# esp_dht.net
KiCad netlist of a schematic drawn in EAGLE
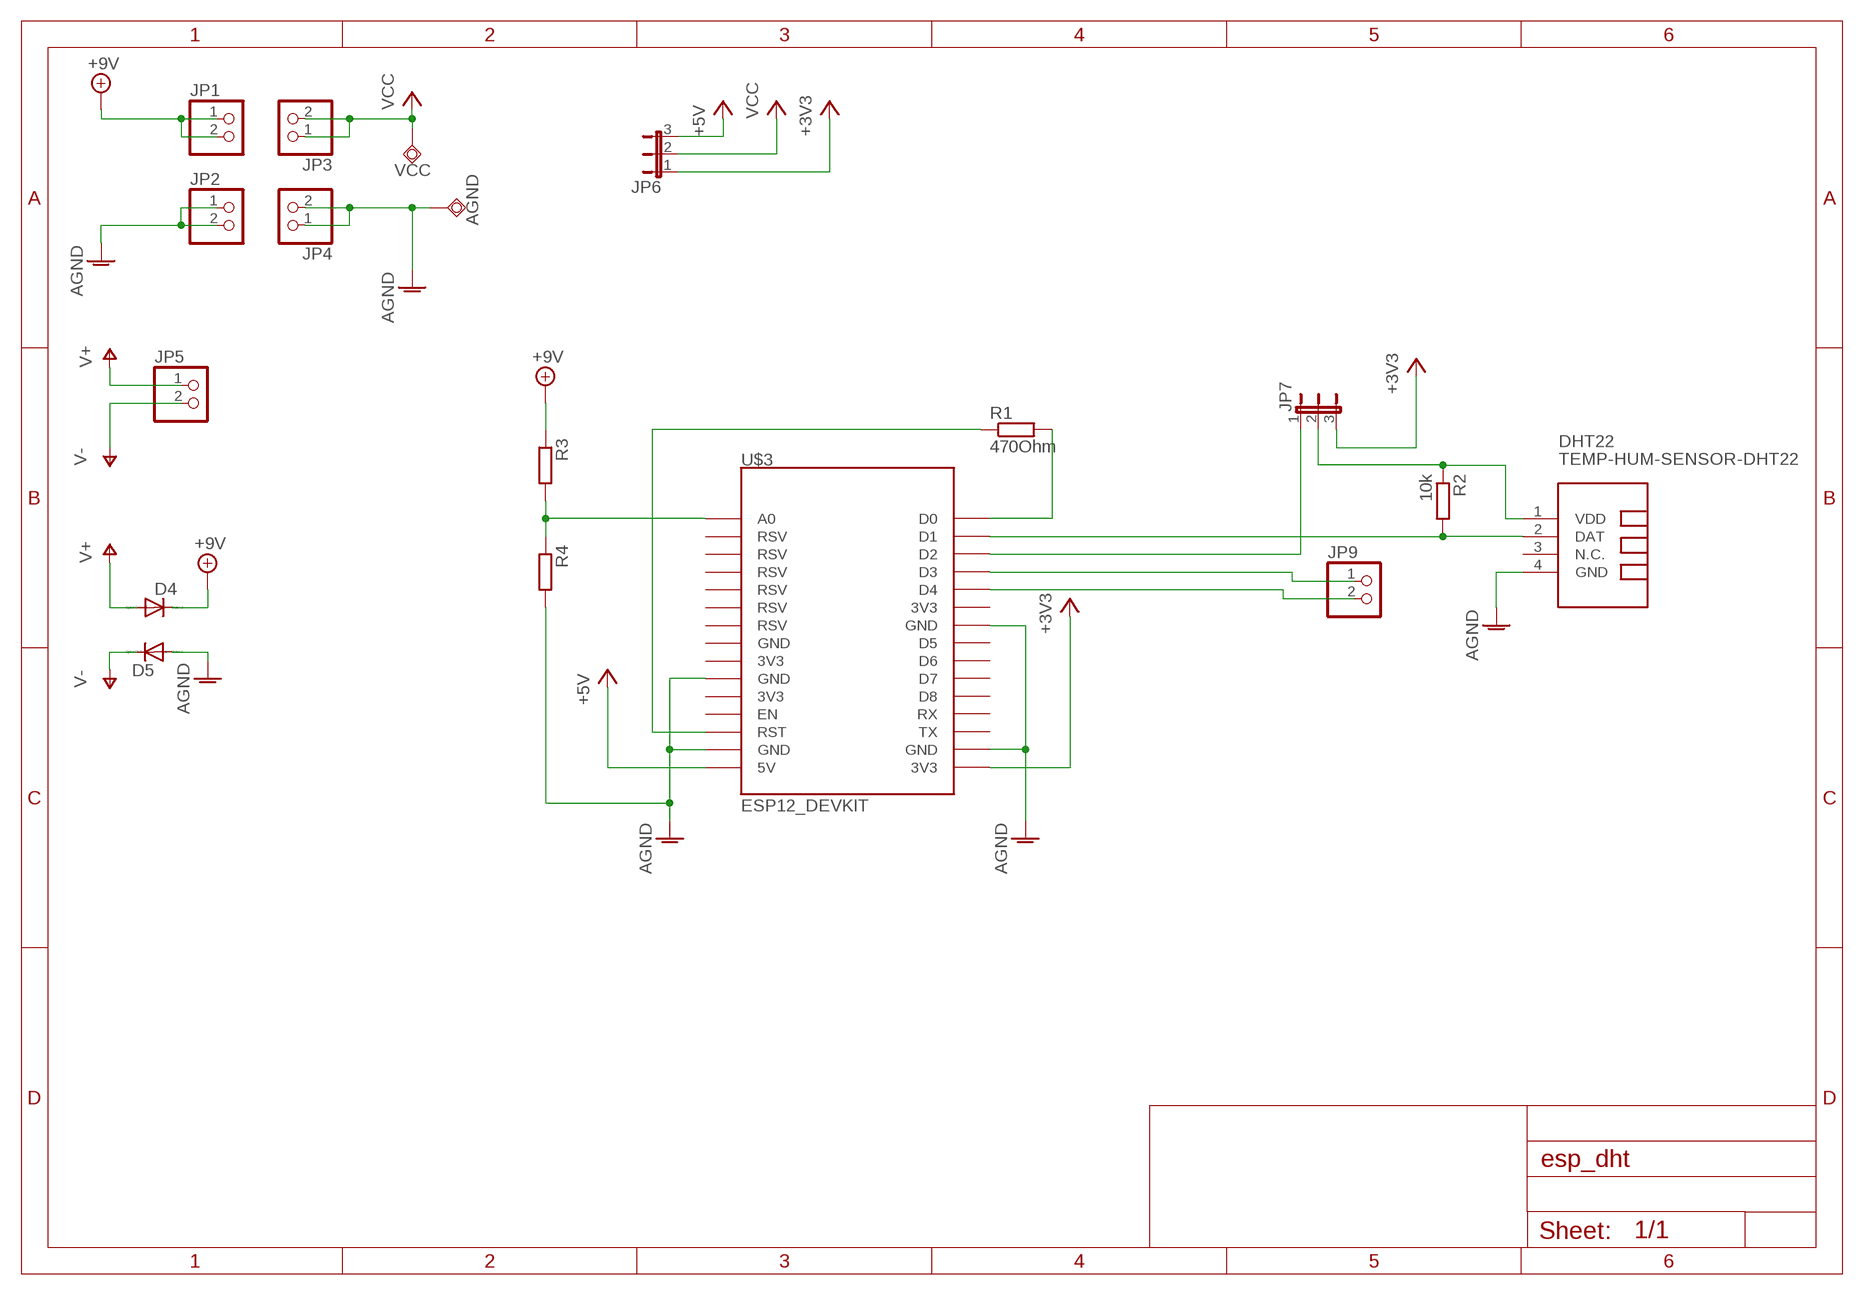
[diagram p0: schematic, sheet 1]

(export (version "E")
  (design (tool "Eeschema 10.0.6"))
  (components
    (comp (ref "AGND")
      (value "TPSQTP20SQ")
      (footprint "eagle-import:TP20SQ")
      (libsource (lib "eagle-import") (part "TPSQTP20SQ"))
    )
    (comp (ref "D4")
      (value "1N4148DO35-7")
      (footprint "eagle-import:DO35-7")
      (libsource (lib "eagle-import") (part "1N4148DO35-7"))
    )
    (comp (ref "D5")
      (value "1N4148DO35-7")
      (footprint "eagle-import:DO35-7")
      (libsource (lib "eagle-import") (part "1N4148DO35-7"))
    )
    (comp (ref "DHT22")
      (value "TEMP-HUM-SENSOR-DHT22")
      (footprint "eagle-import:TEMP-HUM-SENSOR-DHT22")
      (libsource (lib "eagle-import") (part "TEMP-HUM-SENSOR-DHT22"))
    )
    (comp (ref "JP1")
      (value "PINHD-1X2")
      (footprint "eagle-import:1X02")
      (libsource (lib "eagle-import") (part "PINHD-1X2"))
    )
    (comp (ref "JP2")
      (value "PINHD-1X2")
      (footprint "eagle-import:1X02")
      (libsource (lib "eagle-import") (part "PINHD-1X2"))
    )
    (comp (ref "JP3")
      (value "PINHD-1X2")
      (footprint "eagle-import:1X02")
      (libsource (lib "eagle-import") (part "PINHD-1X2"))
    )
    (comp (ref "JP4")
      (value "PINHD-1X2")
      (footprint "eagle-import:1X02")
      (libsource (lib "eagle-import") (part "PINHD-1X2"))
    )
    (comp (ref "JP5")
      (value "PINHD-1X2")
      (footprint "eagle-import:1X02")
      (libsource (lib "eagle-import") (part "PINHD-1X2"))
    )
    (comp (ref "JP6")
      (value "JP2E")
      (footprint "eagle-import:JP2")
      (libsource (lib "eagle-import") (part "JP2E"))
    )
    (comp (ref "JP7")
      (value "JP2E")
      (footprint "eagle-import:JP2")
      (libsource (lib "eagle-import") (part "JP2E"))
    )
    (comp (ref "JP9")
      (value "PINHD-1X2")
      (footprint "eagle-import:1X02")
      (libsource (lib "eagle-import") (part "PINHD-1X2"))
    )
    (comp (ref "R1")
      (value "470Ohm")
      (footprint "eagle-import:R0805")
      (libsource (lib "eagle-import") (part "R-EU_R0805"))
    )
    (comp (ref "R2")
      (value "10k")
      (footprint "eagle-import:R0805")
      (libsource (lib "eagle-import") (part "R-EU_R0805"))
    )
    (comp (ref "R3")
      (value "R-EU_R0805")
      (footprint "eagle-import:R0805")
      (libsource (lib "eagle-import") (part "R-EU_R0805"))
    )
    (comp (ref "R4")
      (value "R-EU_R0805")
      (footprint "eagle-import:R0805")
      (libsource (lib "eagle-import") (part "R-EU_R0805"))
    )
    (comp (ref "U$3")
      (value "ESP12_DEVKIT")
      (footprint "eagle-import:ESP12_DEVKIT")
      (libsource (lib "eagle-import") (part "ESP12_DEVKIT"))
    )
    (comp (ref "VCC")
      (value "TPSQTP20SQ")
      (footprint "eagle-import:TP20SQ")
      (libsource (lib "eagle-import") (part "TPSQTP20SQ"))
    )
  )
  (nets
    (net (code "1") (name "+3V3") (class "Default")
      (node (ref "JP6") (pin "1") (pinfunction "1_1") (pintype "passive"))
      (node (ref "JP7") (pin "3") (pinfunction "3_3") (pintype "passive"))
      (node (ref "U$3") (pin "3V3@2") (pinfunction "3V3_3V3@2") (pintype "bidirectional"))
    )
    (net (code "2") (name "+5V") (class "Default")
      (node (ref "JP6") (pin "3") (pinfunction "3_3") (pintype "passive"))
      (node (ref "U$3") (pin "5V") (pinfunction "5V_5V") (pintype "bidirectional"))
    )
    (net (code "3") (name "+9V") (class "Default")
      (node (ref "D4") (pin "C") (pinfunction "C_C") (pintype "passive"))
      (node (ref "JP1") (pin "1") (pinfunction "1_1") (pintype "passive"))
      (node (ref "JP1") (pin "2") (pinfunction "2_2") (pintype "passive"))
      (node (ref "R3") (pin "1") (pinfunction "1_1") (pintype "passive"))
    )
    (net (code "4") (name "AGND") (class "Default")
      (node (ref "AGND") (pin "TP") (pinfunction "TP_TP") (pintype "input"))
      (node (ref "D5") (pin "A") (pinfunction "A_A") (pintype "passive"))
      (node (ref "DHT22") (pin "4") (pinfunction "GND_4") (pintype "power_in"))
      (node (ref "JP2") (pin "1") (pinfunction "1_1") (pintype "passive"))
      (node (ref "JP2") (pin "2") (pinfunction "2_2") (pintype "passive"))
      (node (ref "JP4") (pin "1") (pinfunction "1_1") (pintype "passive"))
      (node (ref "JP4") (pin "2") (pinfunction "2_2") (pintype "passive"))
      (node (ref "R4") (pin "2") (pinfunction "2_2") (pintype "passive"))
      (node (ref "U$3") (pin "GND@0") (pinfunction "GND_GND@0") (pintype "bidirectional"))
      (node (ref "U$3") (pin "GND@1") (pinfunction "GND_GND@1") (pintype "bidirectional"))
      (node (ref "U$3") (pin "GND@2") (pinfunction "GND_GND@2") (pintype "bidirectional"))
      (node (ref "U$3") (pin "GND@3") (pinfunction "GND_GND@3") (pintype "bidirectional"))
    )
    (net (code "5") (name "Net-(DHT22-DAT)") (class "Default")
      (node (ref "DHT22") (pin "2") (pinfunction "DAT_2") (pintype "bidirectional"))
      (node (ref "R2") (pin "2") (pinfunction "2_2") (pintype "passive"))
      (node (ref "U$3") (pin "D1") (pinfunction "D1_D1") (pintype "bidirectional"))
    )
    (net (code "6") (name "Net-(DHT22-VDD)") (class "Default")
      (node (ref "DHT22") (pin "1") (pinfunction "VDD_1") (pintype "power_in"))
      (node (ref "JP7") (pin "2") (pinfunction "2_2") (pintype "passive"))
      (node (ref "R2") (pin "1") (pinfunction "1_1") (pintype "passive"))
    )
    (net (code "7") (name "Net-(JP7-Pad1)") (class "Default")
      (node (ref "JP7") (pin "1") (pinfunction "1_1") (pintype "passive"))
      (node (ref "U$3") (pin "D2") (pinfunction "D2_D2") (pintype "bidirectional"))
    )
    (net (code "8") (name "Net-(JP9-Pad1)") (class "Default")
      (node (ref "JP9") (pin "1") (pinfunction "1_1") (pintype "passive"))
      (node (ref "U$3") (pin "D3") (pinfunction "D3_D3") (pintype "bidirectional"))
    )
    (net (code "9") (name "Net-(JP9-Pad2)") (class "Default")
      (node (ref "JP9") (pin "2") (pinfunction "2_2") (pintype "passive"))
      (node (ref "U$3") (pin "D4") (pinfunction "D4_D4") (pintype "bidirectional"))
    )
    (net (code "10") (name "Net-(R1-Pad1)") (class "Default")
      (node (ref "R1") (pin "1") (pinfunction "1_1") (pintype "passive"))
      (node (ref "U$3") (pin "RST") (pinfunction "RST_RST") (pintype "bidirectional"))
    )
    (net (code "11") (name "Net-(R1-Pad2)") (class "Default")
      (node (ref "R1") (pin "2") (pinfunction "2_2") (pintype "passive"))
      (node (ref "U$3") (pin "D0") (pinfunction "D0_D0") (pintype "bidirectional"))
    )
    (net (code "12") (name "Net-(R3-Pad2)") (class "Default")
      (node (ref "R3") (pin "2") (pinfunction "2_2") (pintype "passive"))
      (node (ref "R4") (pin "1") (pinfunction "1_1") (pintype "passive"))
      (node (ref "U$3") (pin "A0") (pinfunction "A0_A0") (pintype "bidirectional"))
    )
    (net (code "13") (name "V+") (class "Default")
      (node (ref "D4") (pin "A") (pinfunction "A_A") (pintype "passive"))
      (node (ref "JP5") (pin "1") (pinfunction "1_1") (pintype "passive"))
    )
    (net (code "14") (name "V-") (class "Default")
      (node (ref "D5") (pin "C") (pinfunction "C_C") (pintype "passive"))
      (node (ref "JP5") (pin "2") (pinfunction "2_2") (pintype "passive"))
    )
    (net (code "15") (name "VCC") (class "Default")
      (node (ref "JP3") (pin "1") (pinfunction "1_1") (pintype "passive"))
      (node (ref "JP3") (pin "2") (pinfunction "2_2") (pintype "passive"))
      (node (ref "JP6") (pin "2") (pinfunction "2_2") (pintype "passive"))
      (node (ref "VCC") (pin "TP") (pinfunction "TP_TP") (pintype "input"))
    )
    (net (code "16") (name "unconnected-(DHT22-N.C.-Pad3)") (class "Default")
      (node (ref "DHT22") (pin "3") (pinfunction "N.C._3") (pintype "passive"))
    )
    (net (code "17") (name "unconnected-(U$3-3V3-Pad3V3@0)") (class "Default")
      (node (ref "U$3") (pin "3V3@0") (pinfunction "3V3_3V3@0") (pintype "bidirectional"))
    )
    (net (code "18") (name "unconnected-(U$3-3V3-Pad3V3@1)") (class "Default")
      (node (ref "U$3") (pin "3V3@1") (pinfunction "3V3_3V3@1") (pintype "bidirectional"))
    )
    (net (code "19") (name "unconnected-(U$3-3V3-Pad3V3@3)") (class "Default")
      (node (ref "U$3") (pin "3V3@3") (pinfunction "3V3_3V3@3") (pintype "bidirectional"))
    )
    (net (code "20") (name "unconnected-(U$3-GND-PadGND@4)") (class "Default")
      (node (ref "U$3") (pin "GND@4") (pinfunction "GND_GND@4") (pintype "bidirectional"))
    )
    (net (code "21") (name "unconnected-(U$3-PadD5)") (class "Default")
      (node (ref "U$3") (pin "D5") (pinfunction "D5_D5") (pintype "bidirectional"))
    )
    (net (code "22") (name "unconnected-(U$3-PadD6)") (class "Default")
      (node (ref "U$3") (pin "D6") (pinfunction "D6_D6") (pintype "bidirectional"))
    )
    (net (code "23") (name "unconnected-(U$3-PadD7)") (class "Default")
      (node (ref "U$3") (pin "D7") (pinfunction "D7_D7") (pintype "bidirectional"))
    )
    (net (code "24") (name "unconnected-(U$3-PadD8)") (class "Default")
      (node (ref "U$3") (pin "D8") (pinfunction "D8_D8") (pintype "bidirectional"))
    )
    (net (code "25") (name "unconnected-(U$3-PadEN)") (class "Default")
      (node (ref "U$3") (pin "EN") (pinfunction "EN_EN") (pintype "bidirectional"))
    )
    (net (code "26") (name "unconnected-(U$3-PadRX)") (class "Default")
      (node (ref "U$3") (pin "RX") (pinfunction "RX_RX") (pintype "bidirectional"))
    )
    (net (code "27") (name "unconnected-(U$3-PadTX)") (class "Default")
      (node (ref "U$3") (pin "TX") (pinfunction "TX_TX") (pintype "bidirectional"))
    )
    (net (code "28") (name "unconnected-(U$3-RSV-PadRSV@0)") (class "Default")
      (node (ref "U$3") (pin "RSV@0") (pinfunction "RSV_RSV@0") (pintype "bidirectional"))
    )
    (net (code "29") (name "unconnected-(U$3-RSV-PadRSV@1)") (class "Default")
      (node (ref "U$3") (pin "RSV@1") (pinfunction "RSV_RSV@1") (pintype "bidirectional"))
    )
    (net (code "30") (name "unconnected-(U$3-RSV-PadRSV@2)") (class "Default")
      (node (ref "U$3") (pin "RSV@2") (pinfunction "RSV_RSV@2") (pintype "bidirectional"))
    )
    (net (code "31") (name "unconnected-(U$3-RSV-PadRSV@3)") (class "Default")
      (node (ref "U$3") (pin "RSV@3") (pinfunction "RSV_RSV@3") (pintype "bidirectional"))
    )
    (net (code "32") (name "unconnected-(U$3-RSV-PadRSV@4)") (class "Default")
      (node (ref "U$3") (pin "RSV@4") (pinfunction "RSV_RSV@4") (pintype "bidirectional"))
    )
    (net (code "33") (name "unconnected-(U$3-RSV-PadRSV@5)") (class "Default")
      (node (ref "U$3") (pin "RSV@5") (pinfunction "RSV_RSV@5") (pintype "bidirectional"))
    )
  )
)
